# Sheet4.net
KiCad netlist of a schematic drawn in Altium Designer
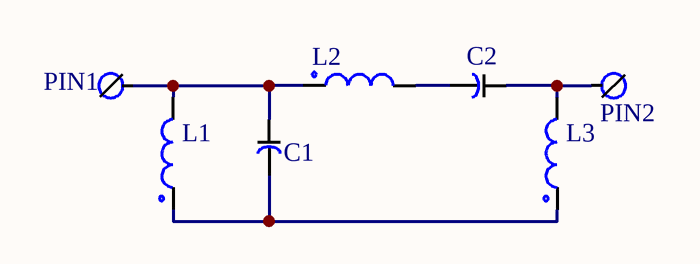
[diagram p0: Sheet4.SchDoc]

(export (version "E")
  (design (tool "Eeschema 10.0.6"))
  (components
    (comp (ref "C1") (value "C1,C3") (footprint "C1,C3") (libsource (lib "Schlib4") (part "C1,C3")))
    (comp (ref "C2") (value "C2") (footprint "C2") (libsource (lib "Schlib4") (part "C2")))
    (comp (ref "L1") (value "L1,L2,L3") (footprint "L1,L2,L3") (libsource (lib "Schlib4") (part "L1,L2,L3")))
    (comp (ref "L2") (value "L1,L2,L3") (footprint "L1,L2,L3") (libsource (lib "Schlib4") (part "L1,L2,L3")))
    (comp (ref "L3") (value "L1,L2,L3") (footprint "L1,L2,L3") (libsource (lib "Schlib4") (part "L1,L2,L3")))
    (comp (ref "PIN1") (value "PIN") (footprint "PIN") (libsource (lib "Schlib4") (part "PIN")))
    (comp (ref "PIN2") (value "PIN") (footprint "PIN") (libsource (lib "Schlib4") (part "PIN")))
  )
  (nets
    (net (code "1") (name "Net-(C1-Pad1)") (class "Default")
      (node (ref "C1") (pin "1") (pinfunction "1_1") (pintype "passive"))
      (node (ref "L1") (pin "1") (pinfunction "1_1") (pintype "passive"))
      (node (ref "L3") (pin "1") (pinfunction "1_1") (pintype "passive"))
    )
    (net (code "2") (name "Net-(C1-Pad2)") (class "Default")
      (node (ref "C1") (pin "2") (pinfunction "2_2") (pintype "passive"))
      (node (ref "L1") (pin "2") (pinfunction "2_2") (pintype "passive"))
      (node (ref "L2") (pin "1") (pinfunction "1_1") (pintype "passive"))
      (node (ref "PIN1") (pin "1") (pinfunction "1_1") (pintype "passive"))
    )
    (net (code "3") (name "Net-(C2-Pad1)") (class "Default")
      (node (ref "C2") (pin "1") (pinfunction "1_1") (pintype "passive"))
      (node (ref "L2") (pin "2") (pinfunction "2_2") (pintype "passive"))
    )
    (net (code "4") (name "Net-(C2-Pad2)") (class "Default")
      (node (ref "C2") (pin "2") (pinfunction "2_2") (pintype "passive"))
      (node (ref "L3") (pin "2") (pinfunction "2_2") (pintype "passive"))
      (node (ref "PIN2") (pin "1") (pinfunction "1_1") (pintype "passive"))
    )
  )
)
